# stm8s003_esc.net
KiCad netlist of a schematic drawn in EAGLE
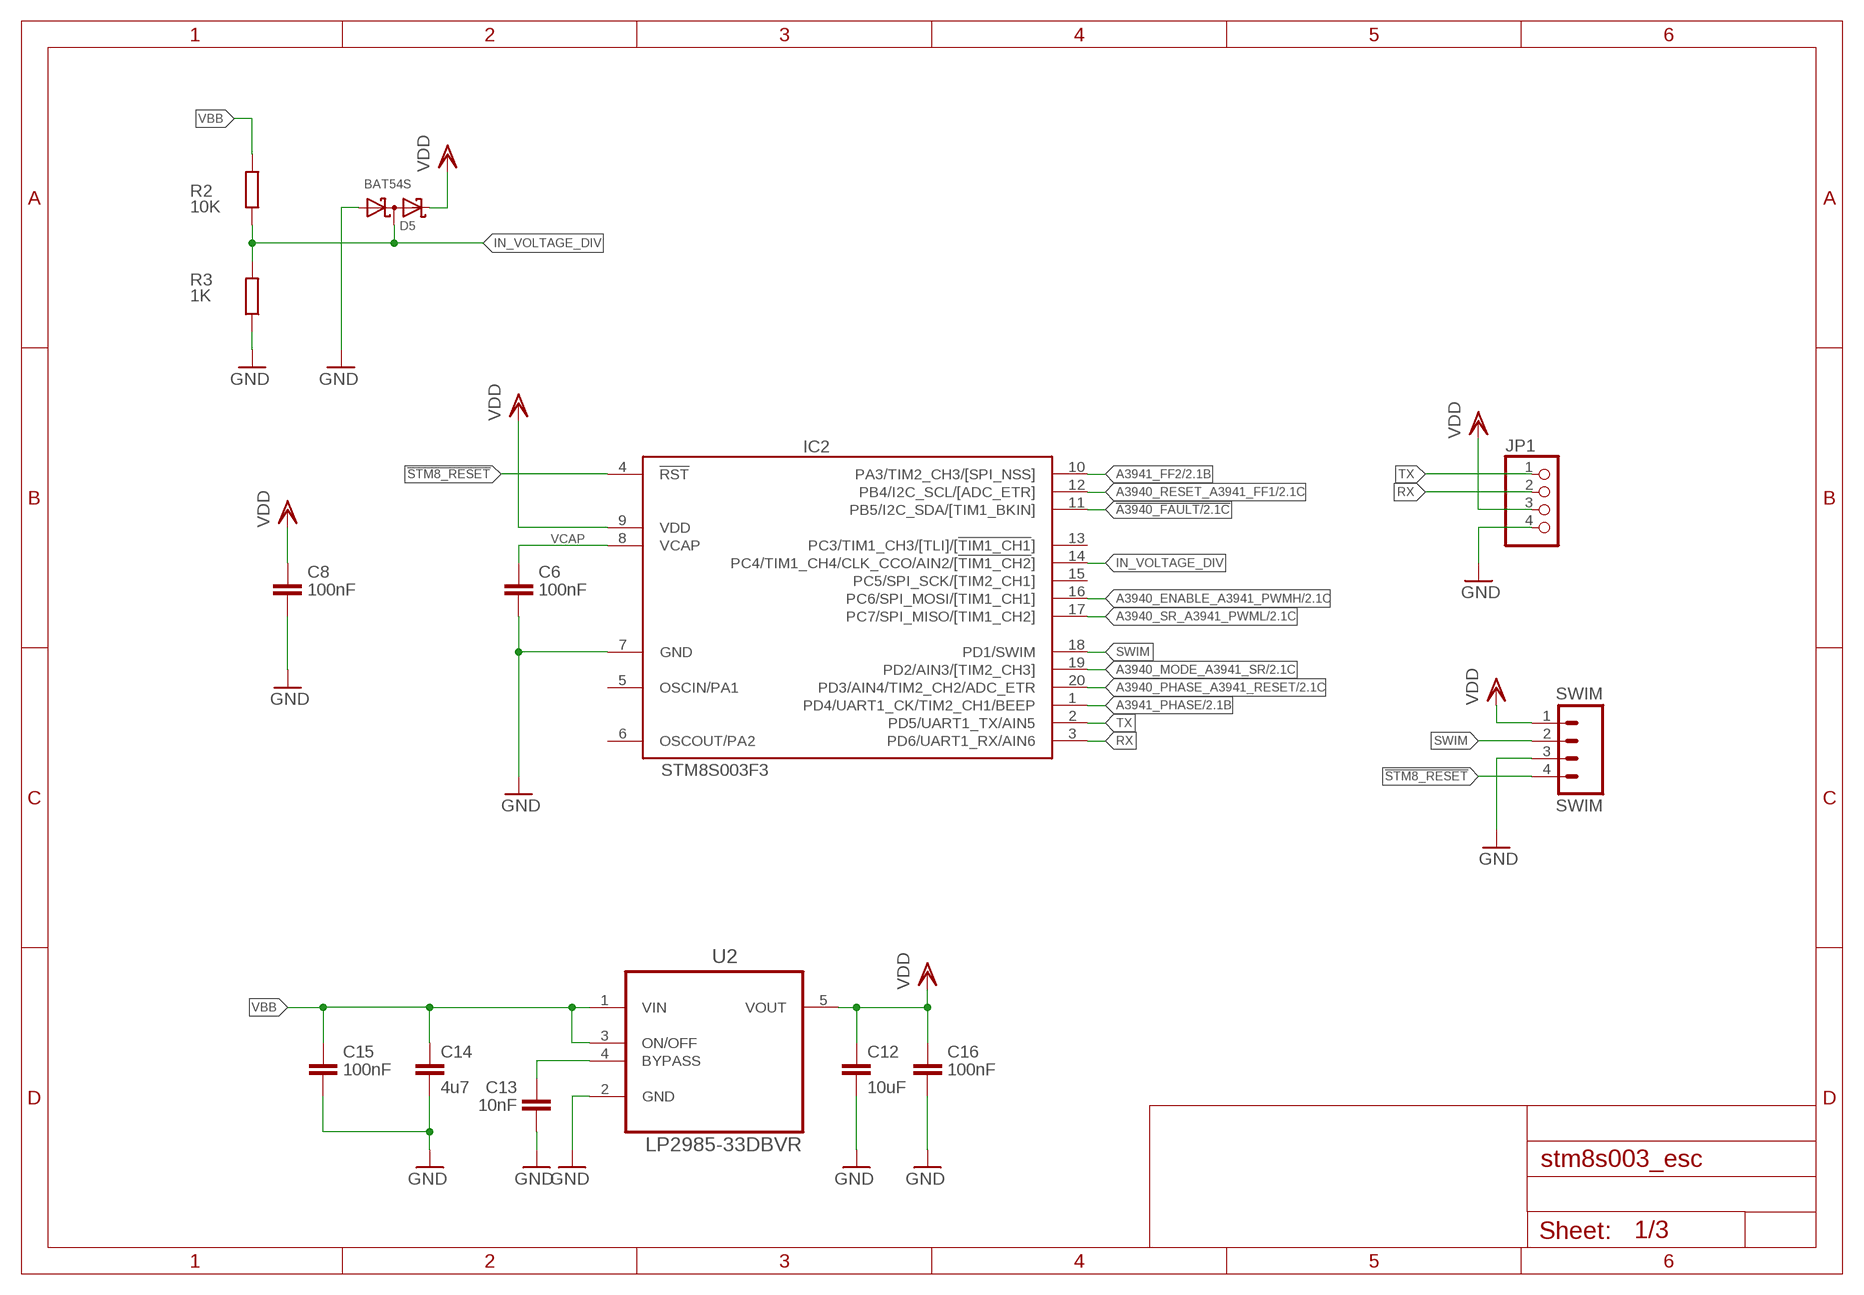
[diagram p0: schematic, sheet 1]
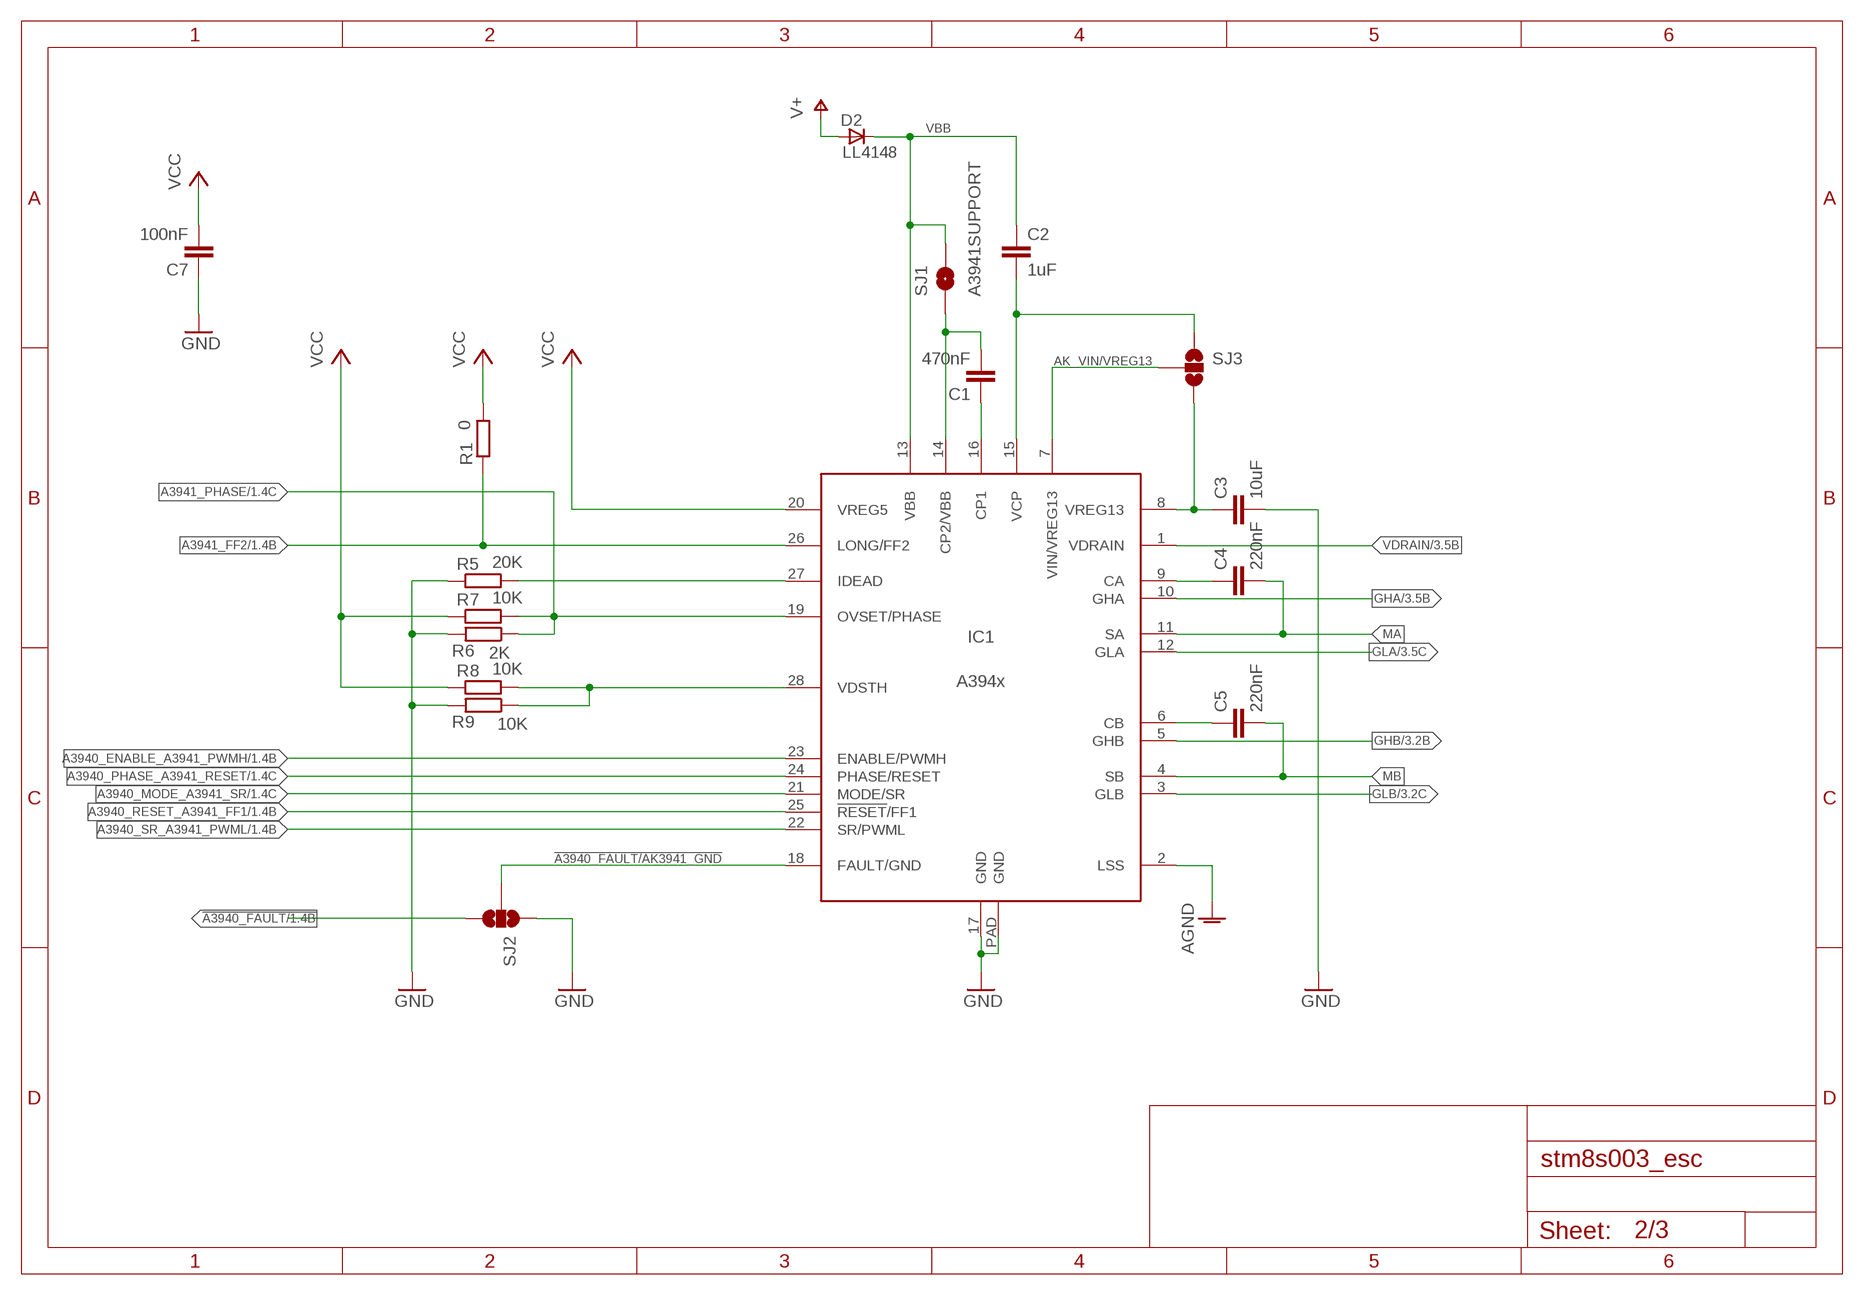
[diagram p1: schematic, sheet 2]
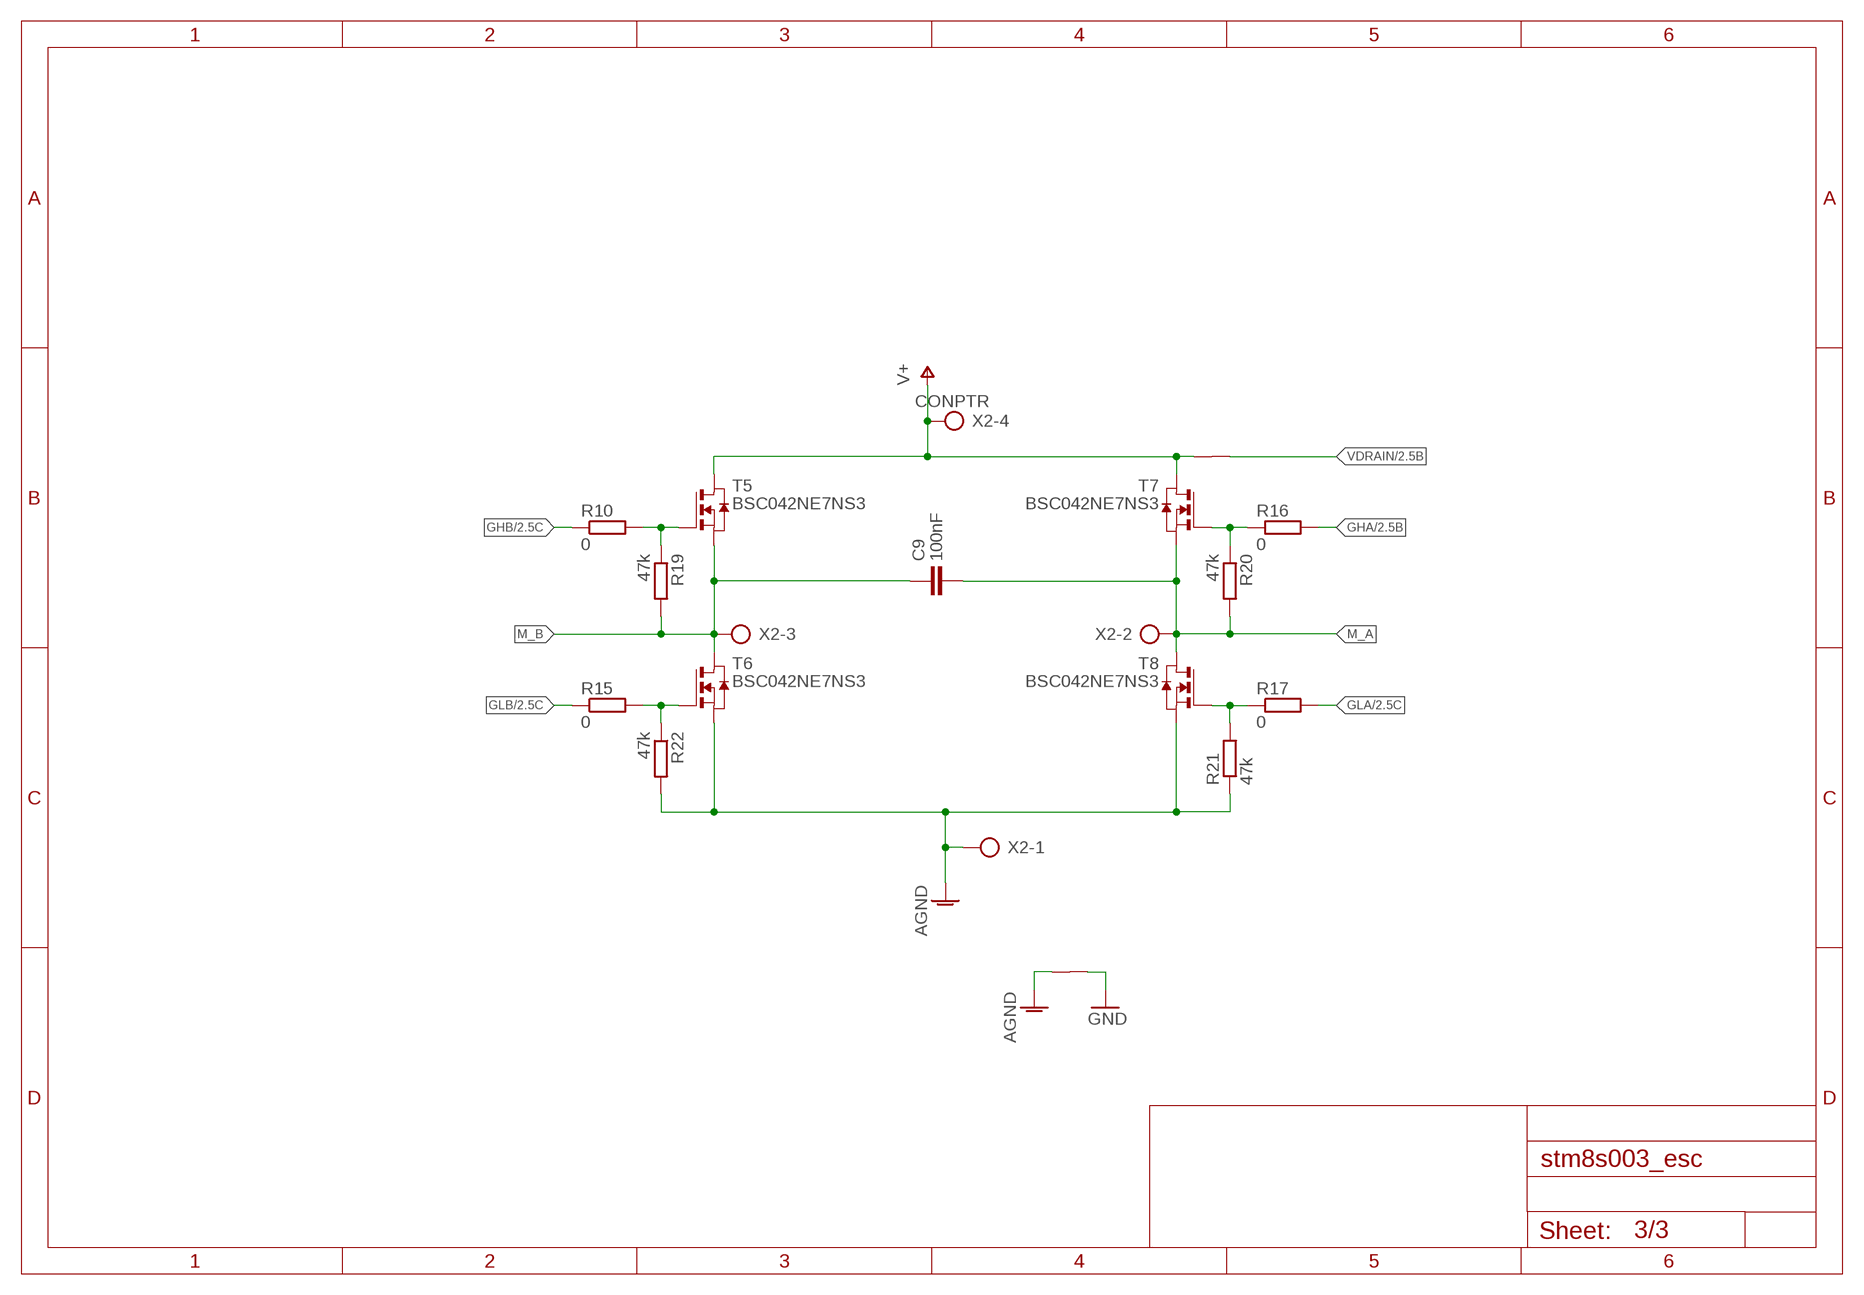
[diagram p2: schematic, sheet 3]

(export (version "E")
  (design (tool "Eeschema 10.0.6"))
  (components
    (comp (ref "C1")
      (value "470nF")
      (footprint "eagle-import:C0603")
      (libsource (lib "eagle-import") (part "resistor_C-EUC0603"))
    )
    (comp (ref "C2")
      (value "1uF")
      (footprint "eagle-import:C0603")
      (libsource (lib "eagle-import") (part "resistor_C-EUC0603"))
    )
    (comp (ref "C3")
      (value "10uF")
      (footprint "eagle-import:C0603")
      (libsource (lib "eagle-import") (part "resistor_C-EUC0603"))
    )
    (comp (ref "C4")
      (value "220nF")
      (footprint "eagle-import:C0603")
      (libsource (lib "eagle-import") (part "resistor_C-EUC0603"))
    )
    (comp (ref "C5")
      (value "220nF")
      (footprint "eagle-import:C0603")
      (libsource (lib "eagle-import") (part "resistor_C-EUC0603"))
    )
    (comp (ref "C7")
      (value "100nF")
      (footprint "eagle-import:C0603")
      (libsource (lib "eagle-import") (part "resistor_C-EUC0603"))
    )
    (comp (ref "D2")
      (value "LL4148")
      (footprint "eagle-import:SOD80_DO213AA_MINIMELF")
      (libsource (lib "eagle-import") (part "LL4148"))
    )
    (comp (ref "IC1")
      (value "A394x")
      (footprint "eagle-import:TSSOP28-PAD")
      (libsource (lib "eagle-import") (part "A3940/41"))
    )
    (comp (ref "R1")
      (value "0")
      (footprint "eagle-import:R0603")
      (libsource (lib "eagle-import") (part "R-EU_R0603"))
    )
    (comp (ref "R5")
      (value "20K")
      (footprint "eagle-import:R0603")
      (libsource (lib "eagle-import") (part "R-EU_R0603"))
    )
    (comp (ref "R6")
      (value "2K")
      (footprint "eagle-import:R0603")
      (libsource (lib "eagle-import") (part "R-EU_R0603"))
    )
    (comp (ref "R7")
      (value "10K")
      (footprint "eagle-import:R0603")
      (libsource (lib "eagle-import") (part "R-EU_R0603"))
    )
    (comp (ref "R8")
      (value "10K")
      (footprint "eagle-import:R0603")
      (libsource (lib "eagle-import") (part "R-EU_R0603"))
    )
    (comp (ref "R9")
      (value "10K")
      (footprint "eagle-import:R0603")
      (libsource (lib "eagle-import") (part "R-EU_R0603"))
    )
    (comp (ref "SJ1")
      (value "A3941SUPPORT")
      (footprint "eagle-import:SJ_2S-NO")
      (libsource (lib "eagle-import") (part "SOLDERJUMPERNO"))
    )
    (comp (ref "SJ2")
      (value "SOLDERJUMPER_2WAYPASTE2&3")
      (footprint "eagle-import:SJ_3_PASTE2&3")
      (libsource (lib "eagle-import") (part "SOLDERJUMPER_2WAYPASTE2&3"))
    )
    (comp (ref "SJ3")
      (value "SOLDERJUMPER_2WAYPASTE2&3")
      (footprint "eagle-import:SJ_3_PASTE2&3")
      (libsource (lib "eagle-import") (part "SOLDERJUMPER_2WAYPASTE2&3"))
    )
    (comp (ref "C6")
      (value "100nF")
      (footprint "eagle-import:C0603")
      (libsource (lib "eagle-import") (part "C-EUC0603"))
    )
    (comp (ref "C8")
      (value "100nF")
      (footprint "eagle-import:C0603")
      (libsource (lib "eagle-import") (part "C-EUC0603"))
    )
    (comp (ref "C12")
      (value "10uF")
      (footprint "eagle-import:C0805")
      (libsource (lib "eagle-import") (part "C-EUC0805"))
    )
    (comp (ref "C13")
      (value "10nF")
      (footprint "eagle-import:C0603")
      (libsource (lib "eagle-import") (part "C-EUC0603"))
    )
    (comp (ref "C14")
      (value "4u7")
      (footprint "eagle-import:C0805")
      (libsource (lib "eagle-import") (part "C-EUC0805"))
    )
    (comp (ref "C15")
      (value "100nF")
      (footprint "eagle-import:C0603")
      (libsource (lib "eagle-import") (part "C-EUC0603"))
    )
    (comp (ref "C16")
      (value "100nF")
      (footprint "eagle-import:C0603K")
      (libsource (lib "eagle-import") (part "C-EUC0603K"))
    )
    (comp (ref "D5")
      (value "BAT54S")
      (footprint "eagle-import:SOT23")
      (libsource (lib "eagle-import") (part "BAT54S"))
    )
    (comp (ref "IC2")
      (value "STM8S003F3")
      (footprint "eagle-import:TSSOP20")
      (libsource (lib "eagle-import") (part "STM8S003F3"))
    )
    (comp (ref "JP1")
      (value "PINHD-1X4")
      (footprint "eagle-import:1X04")
      (libsource (lib "eagle-import") (part "PINHD-1X4"))
    )
    (comp (ref "R2")
      (value "10K")
      (footprint "eagle-import:R0603")
      (libsource (lib "eagle-import") (part "R-EU_R0603"))
    )
    (comp (ref "R3")
      (value "1K")
      (footprint "eagle-import:R0603")
      (libsource (lib "eagle-import") (part "R-EU_R0603"))
    )
    (comp (ref "SWIM")
      (value "SWIM")
      (footprint "eagle-import:1X04-1.27MM")
      (libsource (lib "eagle-import") (part "M041.27MM"))
    )
    (comp (ref "U2")
      (value "LP2985-33DBVR")
      (footprint "eagle-import:SOT95P284X119-5N")
      (fields (field (name "MPN") "LP2985AIM5-3.3"))
      (libsource (lib "eagle-import") (part "LP2985AIM5-3.3"))
    )
    (comp (ref "C9")
      (value "100nF")
      (footprint "eagle-import:C0603")
      (libsource (lib "eagle-import") (part "C-EUC0603"))
    )
    (comp (ref "GND_JUNCTION")
      (value "AGND_DGND_JUNCTION")
      (footprint "eagle-import:AGND_DGND_JUNCTION")
      (libsource (lib "eagle-import") (part "AGND_DGND_JUNCTION"))
    )
    (comp (ref "R10")
      (value "0")
      (footprint "eagle-import:R0603")
      (libsource (lib "eagle-import") (part "R-EU_R0603"))
    )
    (comp (ref "R15")
      (value "0")
      (footprint "eagle-import:R0603")
      (libsource (lib "eagle-import") (part "R-EU_R0603"))
    )
    (comp (ref "R16")
      (value "0")
      (footprint "eagle-import:R0603")
      (libsource (lib "eagle-import") (part "R-EU_R0603"))
    )
    (comp (ref "R17")
      (value "0")
      (footprint "eagle-import:R0603")
      (libsource (lib "eagle-import") (part "R-EU_R0603"))
    )
    (comp (ref "R19")
      (value "47k")
      (footprint "eagle-import:R0603")
      (libsource (lib "eagle-import") (part "R-EU_R0603"))
    )
    (comp (ref "R20")
      (value "47k")
      (footprint "eagle-import:R0603")
      (libsource (lib "eagle-import") (part "R-EU_R0603"))
    )
    (comp (ref "R21")
      (value "47k")
      (footprint "eagle-import:R0603")
      (libsource (lib "eagle-import") (part "R-EU_R0603"))
    )
    (comp (ref "R22")
      (value "47k")
      (footprint "eagle-import:R0603")
      (libsource (lib "eagle-import") (part "R-EU_R0603"))
    )
    (comp (ref "T5")
      (value "BSC042NE7NS3")
      (footprint "eagle-import:PG-TDSON-8")
      (libsource (lib "eagle-import") (part "BSC067N06LS3_G_PG-TDSON-8"))
    )
    (comp (ref "T6")
      (value "BSC042NE7NS3")
      (footprint "eagle-import:PG-TDSON-8")
      (libsource (lib "eagle-import") (part "BSC067N06LS3_G_PG-TDSON-8"))
    )
    (comp (ref "T7")
      (value "BSC042NE7NS3")
      (footprint "eagle-import:PG-TDSON-8")
      (libsource (lib "eagle-import") (part "BSC067N06LS3_G_PG-TDSON-8"))
    )
    (comp (ref "T8")
      (value "BSC042NE7NS3")
      (footprint "eagle-import:PG-TDSON-8")
      (libsource (lib "eagle-import") (part "BSC067N06LS3_G_PG-TDSON-8"))
    )
    (comp (ref "V+_JUNCTION")
      (value "AGND_DGND_JUNCTION")
      (footprint "eagle-import:AGND_DGND_JUNCTION")
      (libsource (lib "eagle-import") (part "AGND_DGND_JUNCTION"))
    )
    (comp (ref "X2")
      (value "CONPTR")
      (footprint "eagle-import:AK300_4")
      (libsource (lib "eagle-import") (part "AK300/4"))
    )
  )
  (nets
    (net (code "1") (name "A3940_ENABLE_A3941_PWMH") (class "Default")
      (node (ref "IC1") (pin "23") (pinfunction "ENABLE/PWMH_23") (pintype "input"))
      (node (ref "IC2") (pin "16") (pinfunction "PC6/SPI_MOSI/[TIM1_CH1]_16") (pintype "bidirectional"))
    )
    (net (code "2") (name "A3940_MODE_A3941_SR") (class "Default")
      (node (ref "IC1") (pin "21") (pinfunction "MODE/SR_21") (pintype "input"))
      (node (ref "IC2") (pin "19") (pinfunction "PD2/AIN3/[TIM2_CH3]_19") (pintype "bidirectional"))
    )
    (net (code "3") (name "A3940_PHASE_A3941_RESET") (class "Default")
      (node (ref "IC1") (pin "24") (pinfunction "PHASE/RESET_24") (pintype "input"))
      (node (ref "IC2") (pin "20") (pinfunction "PD3/AIN4/TIM2_CH2/ADC_ETR_20") (pintype "bidirectional"))
    )
    (net (code "4") (name "A3940_RESET_A3941_FF1") (class "Default")
      (node (ref "IC1") (pin "25") (pinfunction "~{RESET}/FF1_25") (pintype "input"))
      (node (ref "IC2") (pin "12") (pinfunction "PB4/I2C_SCL/[ADC_ETR]_12") (pintype "bidirectional"))
    )
    (net (code "5") (name "A3940_SR_A3941_PWML") (class "Default")
      (node (ref "IC1") (pin "22") (pinfunction "SR/PWML_22") (pintype "input"))
      (node (ref "IC2") (pin "17") (pinfunction "PC7/SPI_MISO/[TIM1_CH2]_17") (pintype "bidirectional"))
    )
    (net (code "6") (name "A3941_FF2") (class "Default")
      (node (ref "IC1") (pin "26") (pinfunction "LONG/FF2_26") (pintype "input"))
      (node (ref "IC2") (pin "10") (pinfunction "PA3/TIM2_CH3/[SPI_NSS]_10") (pintype "bidirectional"))
      (node (ref "R1") (pin "1") (pinfunction "1_1") (pintype "passive"))
    )
    (net (code "7") (name "A3941_PHASE") (class "Default")
      (node (ref "IC1") (pin "19") (pinfunction "OVSET/PHASE_19") (pintype "input"))
      (node (ref "IC2") (pin "1") (pinfunction "PD4/UART1_CK/TIM2_CH1/BEEP_1") (pintype "bidirectional"))
      (node (ref "R6") (pin "1") (pinfunction "1_1") (pintype "passive"))
      (node (ref "R7") (pin "2") (pinfunction "2_2") (pintype "passive"))
    )
    (net (code "8") (name "AGND") (class "Default")
      (node (ref "GND_JUNCTION") (pin "AGND") (pinfunction "AGND_AGND") (pintype "passive"))
      (node (ref "IC1") (pin "2") (pinfunction "LSS_2") (pintype "power_in"))
      (node (ref "R21") (pin "1") (pinfunction "1_1") (pintype "passive"))
      (node (ref "R22") (pin "2") (pinfunction "2_2") (pintype "passive"))
      (node (ref "T6") (pin "1") (pinfunction "S_1") (pintype "passive"))
      (node (ref "T6") (pin "2") (pinfunction "S_2") (pintype "passive"))
      (node (ref "T6") (pin "3") (pinfunction "S_3") (pintype "passive"))
      (node (ref "T8") (pin "1") (pinfunction "S_1") (pintype "passive"))
      (node (ref "T8") (pin "2") (pinfunction "S_2") (pintype "passive"))
      (node (ref "T8") (pin "3") (pinfunction "S_3") (pintype "passive"))
      (node (ref "X2") (pin "1") (pinfunction "KL_1") (pintype "passive"))
    )
    (net (code "9") (name "AK_VIN{slash}VREG13") (class "Default")
      (node (ref "IC1") (pin "7") (pinfunction "VIN/VREG13_7") (pintype "power_in"))
      (node (ref "SJ3") (pin "2") (pinfunction "2_2") (pintype "passive"))
    )
    (net (code "10") (name "GHA") (class "Default")
      (node (ref "IC1") (pin "10") (pinfunction "GHA_10") (pintype "output"))
      (node (ref "R16") (pin "2") (pinfunction "2_2") (pintype "passive"))
    )
    (net (code "11") (name "GHB") (class "Default")
      (node (ref "IC1") (pin "5") (pinfunction "GHB_5") (pintype "output"))
      (node (ref "R10") (pin "1") (pinfunction "1_1") (pintype "passive"))
    )
    (net (code "12") (name "GLA") (class "Default")
      (node (ref "IC1") (pin "12") (pinfunction "GLA_12") (pintype "output"))
      (node (ref "R17") (pin "2") (pinfunction "2_2") (pintype "passive"))
    )
    (net (code "13") (name "GLB") (class "Default")
      (node (ref "IC1") (pin "3") (pinfunction "GLB_3") (pintype "output"))
      (node (ref "R15") (pin "1") (pinfunction "1_1") (pintype "passive"))
    )
    (net (code "14") (name "GND") (class "Default")
      (node (ref "C12") (pin "2") (pinfunction "2_2") (pintype "passive"))
      (node (ref "C13") (pin "2") (pinfunction "2_2") (pintype "passive"))
      (node (ref "C14") (pin "2") (pinfunction "2_2") (pintype "passive"))
      (node (ref "C15") (pin "2") (pinfunction "2_2") (pintype "passive"))
      (node (ref "C16") (pin "2") (pinfunction "2_2") (pintype "passive"))
      (node (ref "C3") (pin "2") (pinfunction "2_2") (pintype "passive"))
      (node (ref "C6") (pin "2") (pinfunction "2_2") (pintype "passive"))
      (node (ref "C7") (pin "1") (pinfunction "1_1") (pintype "passive"))
      (node (ref "C8") (pin "2") (pinfunction "2_2") (pintype "passive"))
      (node (ref "D5") (pin "1") (pinfunction "A1_1") (pintype "passive"))
      (node (ref "GND_JUNCTION") (pin "DGND") (pinfunction "DGND_DGND") (pintype "passive"))
      (node (ref "IC1") (pin "17") (pinfunction "GND_17") (pintype "power_in"))
      (node (ref "IC1") (pin "PAD") (pinfunction "GND_PAD") (pintype "power_in"))
      (node (ref "IC2") (pin "7") (pinfunction "GND_7") (pintype "power_in"))
      (node (ref "JP1") (pin "4") (pinfunction "4_4") (pintype "passive"))
      (node (ref "R3") (pin "1") (pinfunction "1_1") (pintype "passive"))
      (node (ref "R5") (pin "1") (pinfunction "1_1") (pintype "passive"))
      (node (ref "R6") (pin "2") (pinfunction "2_2") (pintype "passive"))
      (node (ref "R9") (pin "2") (pinfunction "2_2") (pintype "passive"))
      (node (ref "SJ2") (pin "1") (pinfunction "1_1") (pintype "passive"))
      (node (ref "SWIM") (pin "3") (pinfunction "3_3") (pintype "passive"))
      (node (ref "U2") (pin "2") (pinfunction "GND_2") (pintype "passive"))
    )
    (net (code "15") (name "IN_VOLTAGE_DIV") (class "Default")
      (node (ref "D5") (pin "3") (pinfunction "C1A2_3") (pintype "passive"))
      (node (ref "IC2") (pin "14") (pinfunction "PC4/TIM1_CH4/CLK_CCO/AIN2/[~{TIM1_CH2}]_14") (pintype "bidirectional"))
      (node (ref "R2") (pin "1") (pinfunction "1_1") (pintype "passive"))
      (node (ref "R3") (pin "2") (pinfunction "2_2") (pintype "passive"))
    )
    (net (code "16") (name "MA") (class "Default")
      (node (ref "C4") (pin "2") (pinfunction "2_2") (pintype "passive"))
      (node (ref "IC1") (pin "11") (pinfunction "SA_11") (pintype "output"))
    )
    (net (code "17") (name "MB") (class "Default")
      (node (ref "C5") (pin "2") (pinfunction "2_2") (pintype "passive"))
      (node (ref "IC1") (pin "4") (pinfunction "SB_4") (pintype "output"))
    )
    (net (code "18") (name "M_A") (class "Default")
      (node (ref "C9") (pin "2") (pinfunction "2_2") (pintype "passive"))
      (node (ref "R20") (pin "2") (pinfunction "2_2") (pintype "passive"))
      (node (ref "T7") (pin "1") (pinfunction "S_1") (pintype "passive"))
      (node (ref "T7") (pin "2") (pinfunction "S_2") (pintype "passive"))
      (node (ref "T7") (pin "3") (pinfunction "S_3") (pintype "passive"))
      (node (ref "T8") (pin "5") (pinfunction "D_5") (pintype "passive"))
      (node (ref "T8") (pin "6") (pinfunction "D_6") (pintype "passive"))
      (node (ref "T8") (pin "7") (pinfunction "D_7") (pintype "passive"))
      (node (ref "T8") (pin "8") (pinfunction "D_8") (pintype "passive"))
      (node (ref "T8") (pin "D") (pinfunction "D_D") (pintype "passive"))
      (node (ref "X2") (pin "2") (pinfunction "KL_2") (pintype "passive"))
    )
    (net (code "19") (name "M_B") (class "Default")
      (node (ref "C9") (pin "1") (pinfunction "1_1") (pintype "passive"))
      (node (ref "R19") (pin "2") (pinfunction "2_2") (pintype "passive"))
      (node (ref "T5") (pin "1") (pinfunction "S_1") (pintype "passive"))
      (node (ref "T5") (pin "2") (pinfunction "S_2") (pintype "passive"))
      (node (ref "T5") (pin "3") (pinfunction "S_3") (pintype "passive"))
      (node (ref "T6") (pin "5") (pinfunction "D_5") (pintype "passive"))
      (node (ref "T6") (pin "6") (pinfunction "D_6") (pintype "passive"))
      (node (ref "T6") (pin "7") (pinfunction "D_7") (pintype "passive"))
      (node (ref "T6") (pin "8") (pinfunction "D_8") (pintype "passive"))
      (node (ref "T6") (pin "D") (pinfunction "D_D") (pintype "passive"))
      (node (ref "X2") (pin "3") (pinfunction "KL_3") (pintype "passive"))
    )
    (net (code "20") (name "Net-(IC1-CA)") (class "Default")
      (node (ref "C4") (pin "1") (pinfunction "1_1") (pintype "passive"))
      (node (ref "IC1") (pin "9") (pinfunction "CA_9") (pintype "output"))
    )
    (net (code "21") (name "Net-(IC1-CB)") (class "Default")
      (node (ref "C5") (pin "1") (pinfunction "1_1") (pintype "passive"))
      (node (ref "IC1") (pin "6") (pinfunction "CB_6") (pintype "output"))
    )
    (net (code "22") (name "Net-(IC1-CP1)") (class "Default")
      (node (ref "C1") (pin "1") (pinfunction "1_1") (pintype "passive"))
      (node (ref "IC1") (pin "16") (pinfunction "CP1_16") (pintype "bidirectional"))
    )
    (net (code "23") (name "Net-(IC1-CP2{slash}VBB)") (class "Default")
      (node (ref "C1") (pin "2") (pinfunction "2_2") (pintype "passive"))
      (node (ref "IC1") (pin "14") (pinfunction "CP2/VBB_14") (pintype "bidirectional"))
      (node (ref "SJ1") (pin "1") (pinfunction "1_1") (pintype "passive"))
    )
    (net (code "24") (name "Net-(IC1-IDEAD)") (class "Default")
      (node (ref "IC1") (pin "27") (pinfunction "IDEAD_27") (pintype "input"))
      (node (ref "R5") (pin "2") (pinfunction "2_2") (pintype "passive"))
    )
    (net (code "25") (name "Net-(IC1-VCP)") (class "Default")
      (node (ref "C2") (pin "2") (pinfunction "2_2") (pintype "passive"))
      (node (ref "IC1") (pin "15") (pinfunction "VCP_15") (pintype "bidirectional"))
      (node (ref "SJ3") (pin "1") (pinfunction "1_1") (pintype "passive"))
    )
    (net (code "26") (name "Net-(IC1-VDSTH)") (class "Default")
      (node (ref "IC1") (pin "28") (pinfunction "VDSTH_28") (pintype "input"))
      (node (ref "R8") (pin "2") (pinfunction "2_2") (pintype "passive"))
      (node (ref "R9") (pin "1") (pinfunction "1_1") (pintype "passive"))
    )
    (net (code "27") (name "Net-(IC1-VREG13)") (class "Default")
      (node (ref "C3") (pin "1") (pinfunction "1_1") (pintype "passive"))
      (node (ref "IC1") (pin "8") (pinfunction "VREG13_8") (pintype "output"))
      (node (ref "SJ3") (pin "3") (pinfunction "3_3") (pintype "passive"))
    )
    (net (code "28") (name "Net-(T5-G)") (class "Default")
      (node (ref "R10") (pin "2") (pinfunction "2_2") (pintype "passive"))
      (node (ref "R19") (pin "1") (pinfunction "1_1") (pintype "passive"))
      (node (ref "T5") (pin "4") (pinfunction "G_4") (pintype "passive"))
    )
    (net (code "29") (name "Net-(T6-G)") (class "Default")
      (node (ref "R15") (pin "2") (pinfunction "2_2") (pintype "passive"))
      (node (ref "R22") (pin "1") (pinfunction "1_1") (pintype "passive"))
      (node (ref "T6") (pin "4") (pinfunction "G_4") (pintype "passive"))
    )
    (net (code "30") (name "Net-(T7-G)") (class "Default")
      (node (ref "R16") (pin "1") (pinfunction "1_1") (pintype "passive"))
      (node (ref "R20") (pin "1") (pinfunction "1_1") (pintype "passive"))
      (node (ref "T7") (pin "4") (pinfunction "G_4") (pintype "passive"))
    )
    (net (code "31") (name "Net-(T8-G)") (class "Default")
      (node (ref "R17") (pin "1") (pinfunction "1_1") (pintype "passive"))
      (node (ref "R21") (pin "2") (pinfunction "2_2") (pintype "passive"))
      (node (ref "T8") (pin "4") (pinfunction "G_4") (pintype "passive"))
    )
    (net (code "32") (name "Net-(U2-BYPASS)") (class "Default")
      (node (ref "C13") (pin "1") (pinfunction "1_1") (pintype "passive"))
      (node (ref "U2") (pin "4") (pinfunction "BYPASS_4") (pintype "passive"))
    )
    (net (code "33") (name "RX") (class "Default")
      (node (ref "IC2") (pin "3") (pinfunction "PD6/UART1_RX/AIN6_3") (pintype "bidirectional"))
      (node (ref "JP1") (pin "2") (pinfunction "2_2") (pintype "passive"))
    )
    (net (code "34") (name "SWIM") (class "Default")
      (node (ref "IC2") (pin "18") (pinfunction "PD1/SWIM_18") (pintype "bidirectional"))
      (node (ref "SWIM") (pin "2") (pinfunction "2_2") (pintype "passive"))
    )
    (net (code "35") (name "TX") (class "Default")
      (node (ref "IC2") (pin "2") (pinfunction "PD5/UART1_TX/AIN5_2") (pintype "bidirectional"))
      (node (ref "JP1") (pin "1") (pinfunction "1_1") (pintype "passive"))
    )
    (net (code "36") (name "V+") (class "Default")
      (node (ref "D2") (pin "A") (pinfunction "A_A") (pintype "passive"))
      (node (ref "T5") (pin "5") (pinfunction "D_5") (pintype "passive"))
      (node (ref "T5") (pin "6") (pinfunction "D_6") (pintype "passive"))
      (node (ref "T5") (pin "7") (pinfunction "D_7") (pintype "passive"))
      (node (ref "T5") (pin "8") (pinfunction "D_8") (pintype "passive"))
      (node (ref "T5") (pin "D") (pinfunction "D_D") (pintype "passive"))
      (node (ref "T7") (pin "5") (pinfunction "D_5") (pintype "passive"))
      (node (ref "T7") (pin "6") (pinfunction "D_6") (pintype "passive"))
      (node (ref "T7") (pin "7") (pinfunction "D_7") (pintype "passive"))
      (node (ref "T7") (pin "8") (pinfunction "D_8") (pintype "passive"))
      (node (ref "T7") (pin "D") (pinfunction "D_D") (pintype "passive"))
      (node (ref "V+_JUNCTION") (pin "AGND") (pinfunction "AGND_AGND") (pintype "passive"))
      (node (ref "X2") (pin "4") (pinfunction "KL_4") (pintype "passive"))
    )
    (net (code "37") (name "VBB") (class "Default")
      (node (ref "C14") (pin "1") (pinfunction "1_1") (pintype "passive"))
      (node (ref "C15") (pin "1") (pinfunction "1_1") (pintype "passive"))
      (node (ref "C2") (pin "1") (pinfunction "1_1") (pintype "passive"))
      (node (ref "D2") (pin "C") (pinfunction "C_C") (pintype "passive"))
      (node (ref "IC1") (pin "13") (pinfunction "VBB_13") (pintype "power_in"))
      (node (ref "R2") (pin "2") (pinfunction "2_2") (pintype "passive"))
      (node (ref "SJ1") (pin "2") (pinfunction "2_2") (pintype "passive"))
      (node (ref "U2") (pin "1") (pinfunction "VIN_1") (pintype "power_in"))
      (node (ref "U2") (pin "3") (pinfunction "ON/OFF_3") (pintype "input"))
    )
    (net (code "38") (name "VCAP") (class "Default")
      (node (ref "C6") (pin "1") (pinfunction "1_1") (pintype "passive"))
      (node (ref "IC2") (pin "8") (pinfunction "VCAP_8") (pintype "power_in"))
    )
    (net (code "39") (name "VCC") (class "Default")
      (node (ref "C7") (pin "2") (pinfunction "2_2") (pintype "passive"))
      (node (ref "IC1") (pin "20") (pinfunction "VREG5_20") (pintype "power_in"))
      (node (ref "R1") (pin "2") (pinfunction "2_2") (pintype "passive"))
      (node (ref "R7") (pin "1") (pinfunction "1_1") (pintype "passive"))
      (node (ref "R8") (pin "1") (pinfunction "1_1") (pintype "passive"))
    )
    (net (code "40") (name "VDD") (class "Default")
      (node (ref "C12") (pin "1") (pinfunction "1_1") (pintype "passive"))
      (node (ref "C16") (pin "1") (pinfunction "1_1") (pintype "passive"))
      (node (ref "C8") (pin "1") (pinfunction "1_1") (pintype "passive"))
      (node (ref "D5") (pin "2") (pinfunction "C2_2") (pintype "passive"))
      (node (ref "IC2") (pin "9") (pinfunction "VDD_9") (pintype "power_in"))
      (node (ref "JP1") (pin "3") (pinfunction "3_3") (pintype "passive"))
      (node (ref "SWIM") (pin "1") (pinfunction "1_1") (pintype "passive"))
      (node (ref "U2") (pin "5") (pinfunction "VOUT_5") (pintype "passive"))
    )
    (net (code "41") (name "VDRAIN") (class "Default")
      (node (ref "IC1") (pin "1") (pinfunction "VDRAIN_1") (pintype "power_in"))
      (node (ref "V+_JUNCTION") (pin "DGND") (pinfunction "DGND_DGND") (pintype "passive"))
    )
    (net (code "42") (name "unconnected-(IC2-OSCIN{slash}PA1-Pad5)") (class "Default")
      (node (ref "IC2") (pin "5") (pinfunction "OSCIN/PA1_5") (pintype "bidirectional"))
    )
    (net (code "43") (name "unconnected-(IC2-OSCOUT{slash}PA2-Pad6)") (class "Default")
      (node (ref "IC2") (pin "6") (pinfunction "OSCOUT/PA2_6") (pintype "bidirectional"))
    )
    (net (code "44") (name "unconnected-(IC2-PC3{slash}TIM1_CH3{slash}[TLI]{slash}[~{TIM1_CH1}]-Pad13)") (class "Default")
      (node (ref "IC2") (pin "13") (pinfunction "PC3/TIM1_CH3/[TLI]/[~{TIM1_CH1}]_13") (pintype "bidirectional"))
    )
    (net (code "45") (name "unconnected-(IC2-PC5{slash}SPI_SCK{slash}[TIM2_CH1]-Pad15)") (class "Default")
      (node (ref "IC2") (pin "15") (pinfunction "PC5/SPI_SCK/[TIM2_CH1]_15") (pintype "bidirectional"))
    )
    (net (code "46") (name "~{A3940_FAULT{slash}AK3941_GND}") (class "Default")
      (node (ref "IC1") (pin "18") (pinfunction "FAULT/GND_18") (pintype "open_collector"))
      (node (ref "SJ2") (pin "2") (pinfunction "2_2") (pintype "passive"))
    )
    (net (code "47") (name "~{A3940_FAULT}") (class "Default")
      (node (ref "IC2") (pin "11") (pinfunction "PB5/I2C_SDA/[TIM1_BKIN]_11") (pintype "bidirectional"))
      (node (ref "SJ2") (pin "3") (pinfunction "3_3") (pintype "passive"))
    )
    (net (code "48") (name "~{STM8_RESET}") (class "Default")
      (node (ref "IC2") (pin "4") (pinfunction "~{RST}_4") (pintype "input"))
      (node (ref "SWIM") (pin "4") (pinfunction "4_4") (pintype "passive"))
    )
  )
)
